# MPU6050.net
KiCad netlist of a schematic drawn in EAGLE
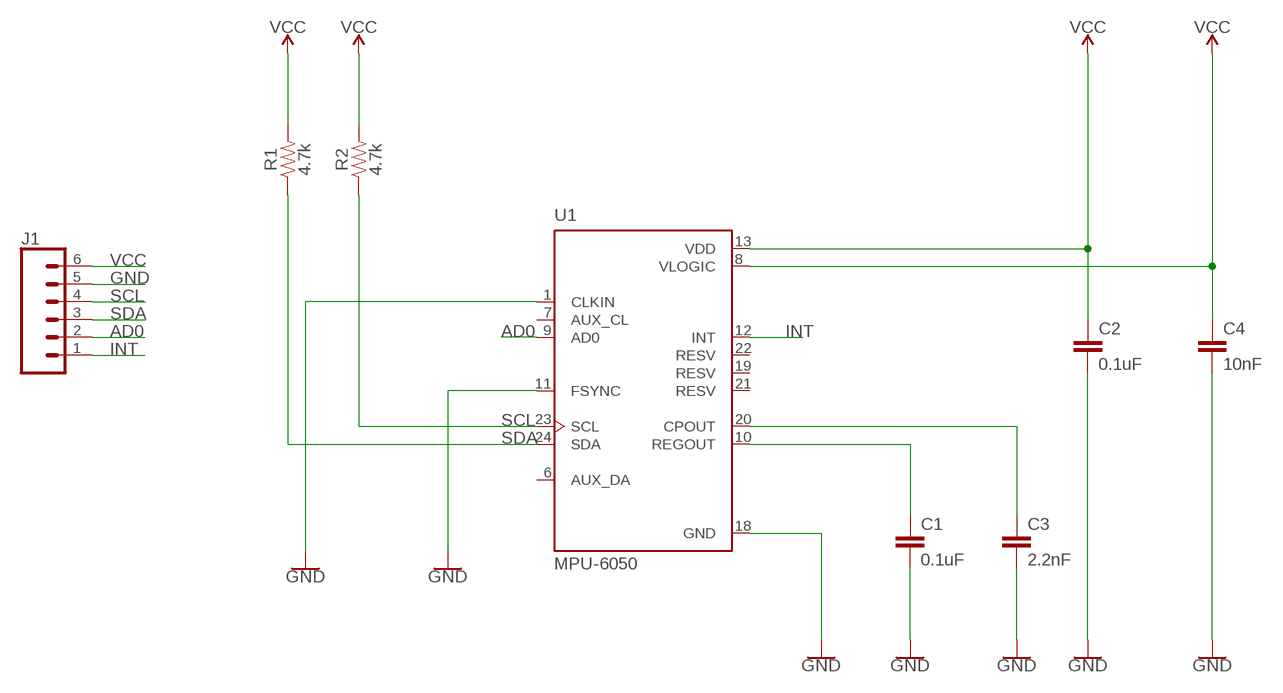
[diagram p0: schematic, sheet 1]

(export (version "E")
  (design (tool "Eeschema 10.0.6"))
  (components
    (comp (ref "C1")
      (value "0.1uF")
      (footprint "eagle-import:0805")
      (libsource (lib "eagle-import") (part "1.0UF-0805-25V-10%"))
    )
    (comp (ref "C2")
      (value "0.1uF")
      (footprint "eagle-import:0805")
      (libsource (lib "eagle-import") (part "1.0UF-0805-25V-10%"))
    )
    (comp (ref "C3")
      (value "2.2nF")
      (footprint "eagle-import:0805")
      (libsource (lib "eagle-import") (part "1.0UF-0805-25V-10%"))
    )
    (comp (ref "C4")
      (value "10nF")
      (footprint "eagle-import:0805")
      (libsource (lib "eagle-import") (part "1.0UF-0805-25V-10%"))
    )
    (comp (ref "J1")
      (value "CONN_06NO_SILK_FEMALE_PTH")
      (footprint "eagle-import:1X06_NO_SILK")
      (libsource (lib "eagle-import") (part "CONN_06NO_SILK_FEMALE_PTH"))
    )
    (comp (ref "R1")
      (value "4.7k")
      (footprint "eagle-import:0805")
      (libsource (lib "eagle-import") (part "RESISTOR0805"))
    )
    (comp (ref "R2")
      (value "4.7k")
      (footprint "eagle-import:0805")
      (libsource (lib "eagle-import") (part "RESISTOR0805"))
    )
    (comp (ref "U1")
      (value "MPU-6050")
      (footprint "eagle-import:QFN50P400X400X95-24N")
      (fields (field (name "DIGI-KEY_PART_NUMBER") "1428-1007-1-ND") (field (name "MF") "TDK InvenSense"))
      (libsource (lib "eagle-import") (part "MPU-6050"))
    )
  )
  (nets
    (net (code "1") (name "/AD0") (class "Default")
      (node (ref "J1") (pin "2") (pinfunction "2_2") (pintype "passive"))
      (node (ref "U1") (pin "9") (pinfunction "AD0_9") (pintype "input"))
    )
    (net (code "2") (name "/INT") (class "Default")
      (node (ref "J1") (pin "1") (pinfunction "1_1") (pintype "passive"))
      (node (ref "U1") (pin "12") (pinfunction "INT_12") (pintype "output"))
    )
    (net (code "3") (name "/SCL") (class "Default")
      (node (ref "J1") (pin "4") (pinfunction "4_4") (pintype "passive"))
      (node (ref "R2") (pin "1") (pinfunction "1_1") (pintype "passive"))
      (node (ref "U1") (pin "23") (pinfunction "SCL_23") (pintype "input"))
    )
    (net (code "4") (name "/SDA") (class "Default")
      (node (ref "J1") (pin "3") (pinfunction "3_3") (pintype "passive"))
      (node (ref "R1") (pin "1") (pinfunction "1_1") (pintype "passive"))
      (node (ref "U1") (pin "24") (pinfunction "SDA_24") (pintype "bidirectional"))
    )
    (net (code "5") (name "GND") (class "Default")
      (node (ref "C1") (pin "2") (pinfunction "2_2") (pintype "passive"))
      (node (ref "C2") (pin "2") (pinfunction "2_2") (pintype "passive"))
      (node (ref "C3") (pin "2") (pinfunction "2_2") (pintype "passive"))
      (node (ref "C4") (pin "2") (pinfunction "2_2") (pintype "passive"))
      (node (ref "J1") (pin "5") (pinfunction "5_5") (pintype "passive"))
      (node (ref "U1") (pin "1") (pinfunction "CLKIN_1") (pintype "input"))
      (node (ref "U1") (pin "11") (pinfunction "FSYNC_11") (pintype "input"))
      (node (ref "U1") (pin "18") (pinfunction "GND_18") (pintype "power_in"))
    )
    (net (code "6") (name "Net-(U1-CPOUT)") (class "Default")
      (node (ref "C3") (pin "1") (pinfunction "1_1") (pintype "passive"))
      (node (ref "U1") (pin "20") (pinfunction "CPOUT_20") (pintype "passive"))
    )
    (net (code "7") (name "Net-(U1-REGOUT)") (class "Default")
      (node (ref "C1") (pin "1") (pinfunction "1_1") (pintype "passive"))
      (node (ref "U1") (pin "10") (pinfunction "REGOUT_10") (pintype "passive"))
    )
    (net (code "8") (name "VCC") (class "Default")
      (node (ref "C2") (pin "1") (pinfunction "1_1") (pintype "passive"))
      (node (ref "C4") (pin "1") (pinfunction "1_1") (pintype "passive"))
      (node (ref "J1") (pin "6") (pinfunction "6_6") (pintype "passive"))
      (node (ref "R1") (pin "2") (pinfunction "2_2") (pintype "passive"))
      (node (ref "R2") (pin "2") (pinfunction "2_2") (pintype "passive"))
      (node (ref "U1") (pin "13") (pinfunction "VDD_13") (pintype "power_in"))
      (node (ref "U1") (pin "8") (pinfunction "VLOGIC_8") (pintype "power_in"))
    )
    (net (code "9") (name "unconnected-(U1-AUX_CL-Pad7)") (class "Default")
      (node (ref "U1") (pin "7") (pinfunction "AUX_CL_7") (pintype "input"))
    )
    (net (code "10") (name "unconnected-(U1-AUX_DA-Pad6)") (class "Default")
      (node (ref "U1") (pin "6") (pinfunction "AUX_DA_6") (pintype "bidirectional"))
    )
    (net (code "11") (name "unconnected-(U1-RESV-Pad19)") (class "Default")
      (node (ref "U1") (pin "19") (pinfunction "RESV_19") (pintype "passive"))
    )
    (net (code "12") (name "unconnected-(U1-RESV-Pad21)") (class "Default")
      (node (ref "U1") (pin "21") (pinfunction "RESV_21") (pintype "passive"))
    )
    (net (code "13") (name "unconnected-(U1-RESV-Pad22)") (class "Default")
      (node (ref "U1") (pin "22") (pinfunction "RESV_22") (pintype "passive"))
    )
  )
)
